# Test_Node.net
KiCad netlist of a schematic drawn in EAGLE
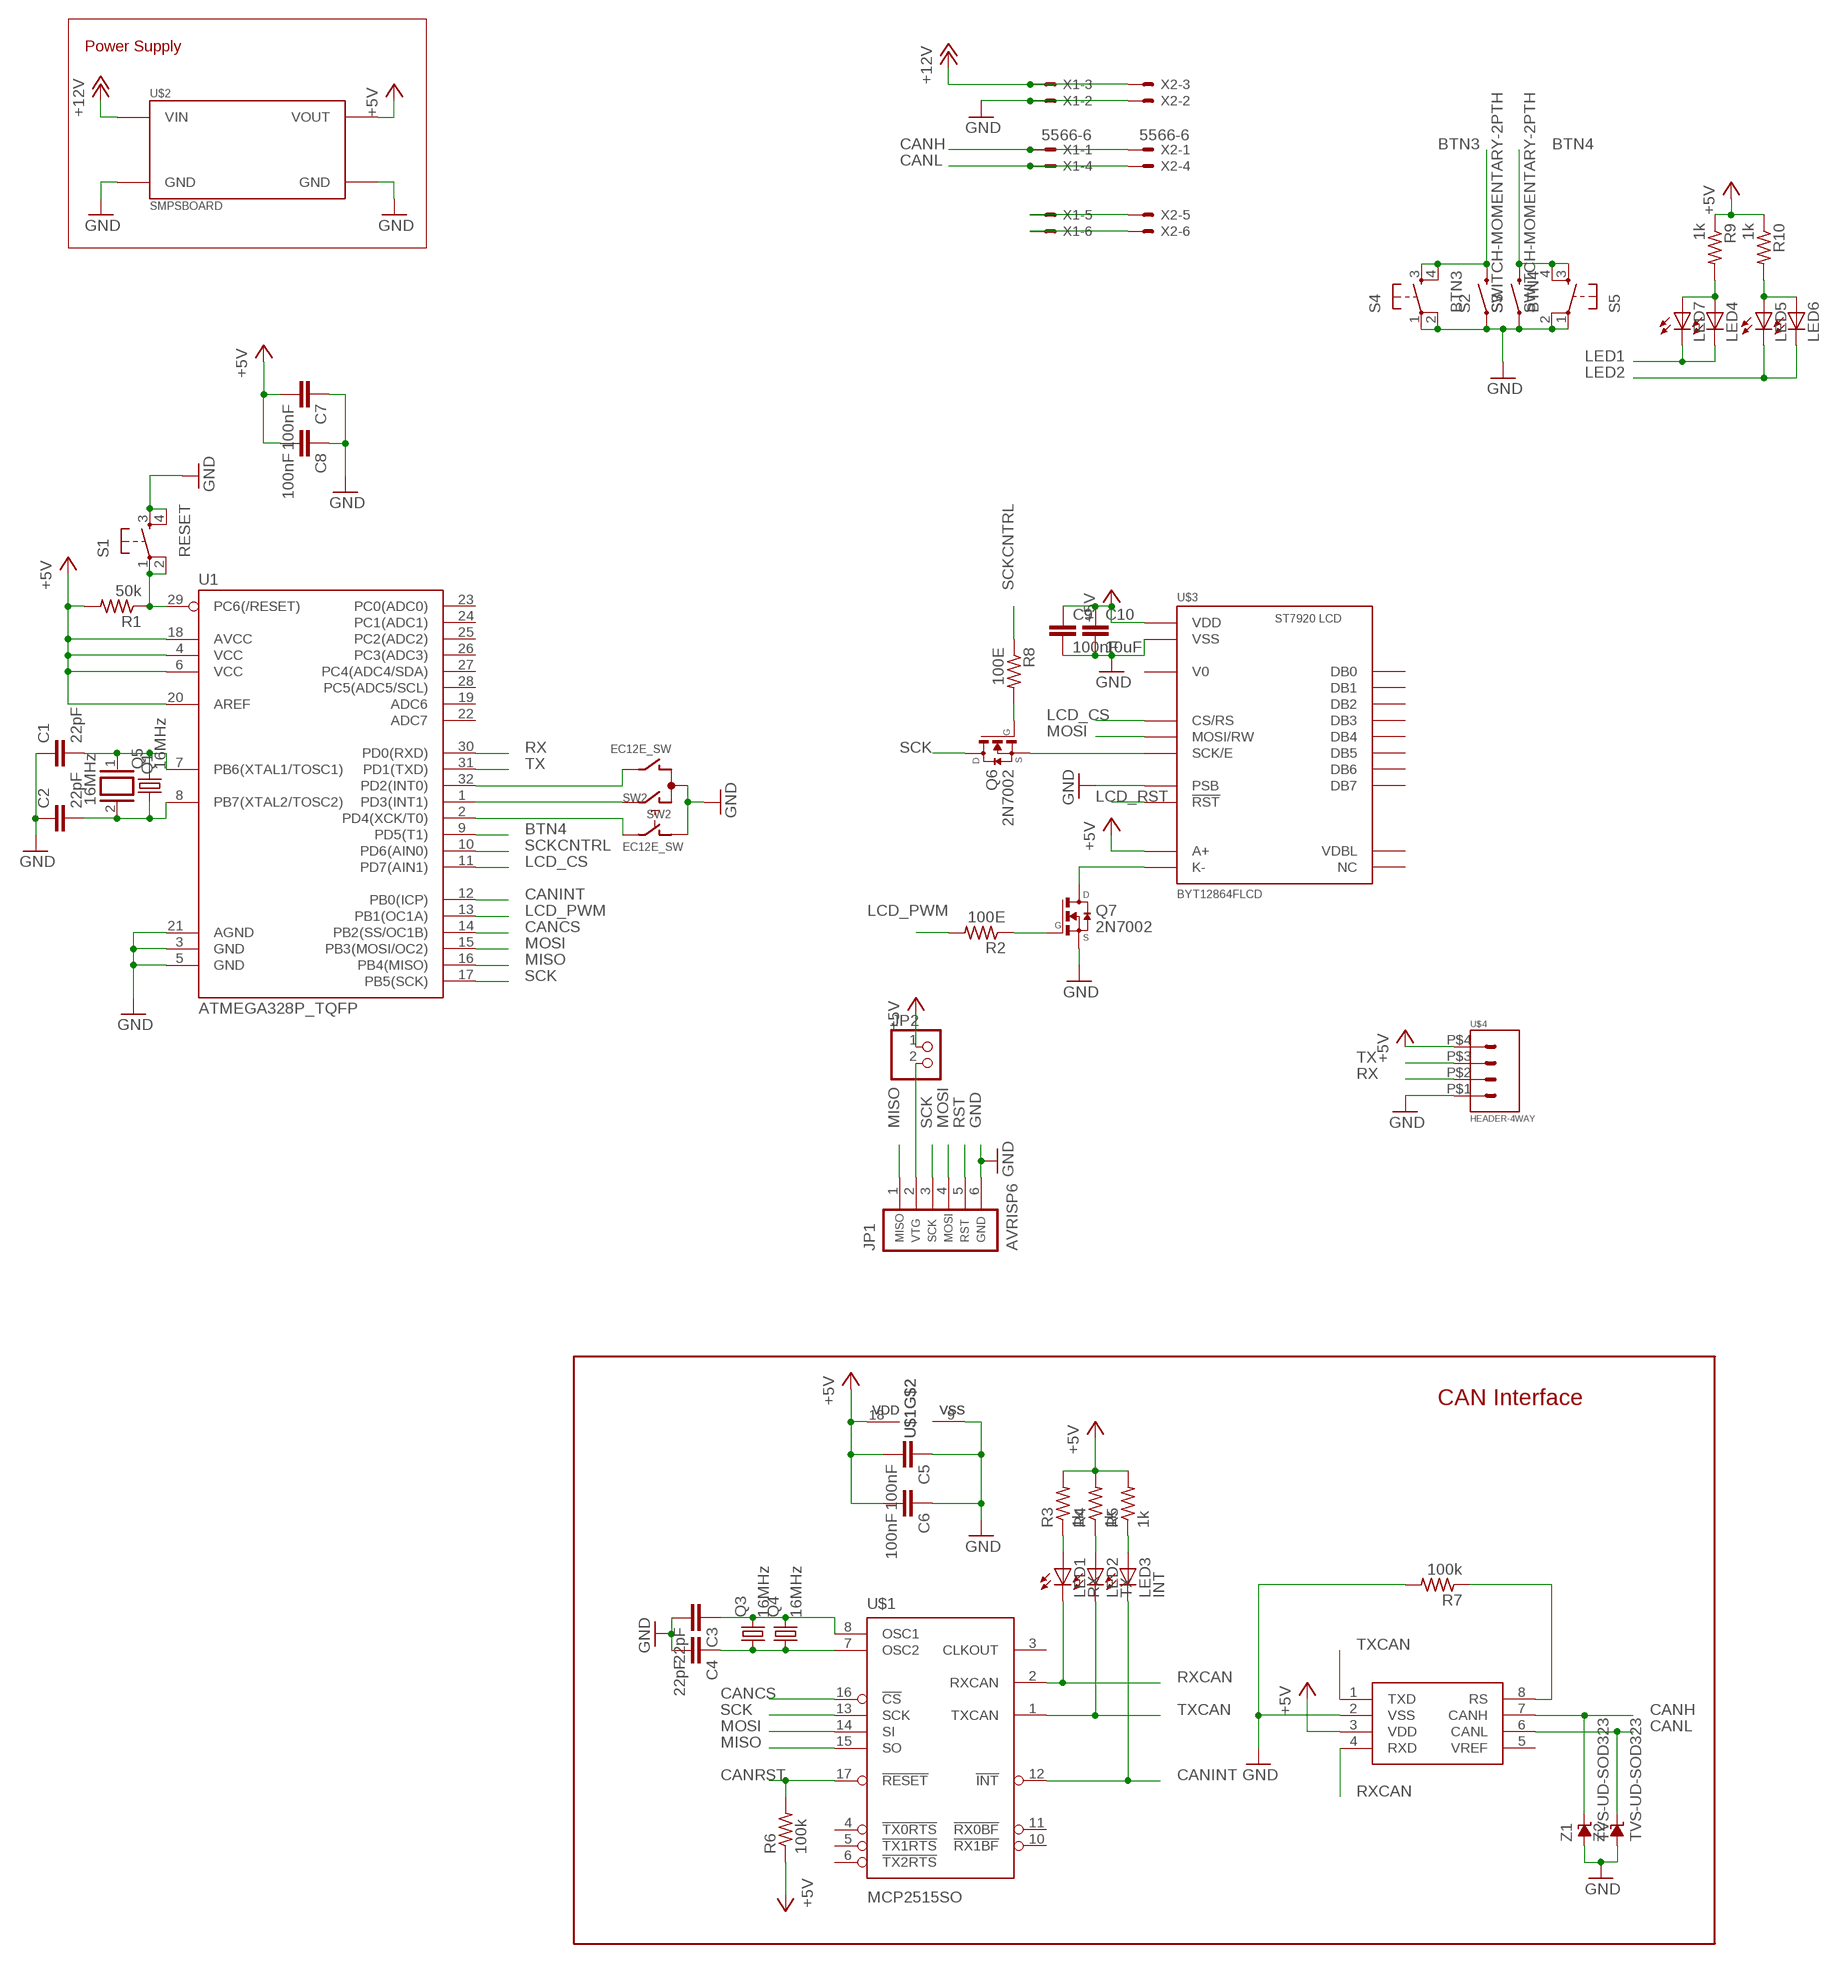
[diagram p0: schematic, sheet 1]

(export (version "E")
  (design (tool "Eeschema 10.0.6"))
  (components
    (comp (ref "C1")
      (value "22pF")
      (footprint "eagle-import:C0805")
      (libsource (lib "eagle-import") (part "C-EUC0805"))
    )
    (comp (ref "C2")
      (value "22pF")
      (footprint "eagle-import:C0805")
      (libsource (lib "eagle-import") (part "C-EUC0805"))
    )
    (comp (ref "C3")
      (value "22pF")
      (footprint "eagle-import:C0805K")
      (libsource (lib "eagle-import") (part "C-EUC0805K"))
    )
    (comp (ref "C4")
      (value "22pF")
      (footprint "eagle-import:C0805K")
      (libsource (lib "eagle-import") (part "C-EUC0805K"))
    )
    (comp (ref "C5")
      (value "100nF")
      (footprint "eagle-import:C0805K")
      (libsource (lib "eagle-import") (part "C-EUC0805K"))
    )
    (comp (ref "C6")
      (value "100nF")
      (footprint "eagle-import:C0805K")
      (libsource (lib "eagle-import") (part "C-EUC0805K"))
    )
    (comp (ref "C7")
      (value "100nF")
      (footprint "eagle-import:C0805")
      (libsource (lib "eagle-import") (part "C-EUC0805"))
    )
    (comp (ref "C8")
      (value "100nF")
      (footprint "eagle-import:C0805")
      (libsource (lib "eagle-import") (part "C-EUC0805"))
    )
    (comp (ref "C9")
      (value "100nF")
      (footprint "eagle-import:C0805")
      (libsource (lib "eagle-import") (part "C-EUC0805"))
    )
    (comp (ref "C10")
      (value "10uF")
      (footprint "eagle-import:C0805")
      (libsource (lib "eagle-import") (part "C-EUC0805"))
    )
    (comp (ref "JP1")
      (value "AVRISP6")
      (footprint "eagle-import:HDR-75869-131")
      (libsource (lib "eagle-import") (part "AVR-ISP6-75869-131"))
    )
    (comp (ref "JP2")
      (value "PINHD-1X2")
      (footprint "eagle-import:1X02")
      (libsource (lib "eagle-import") (part "PINHD-1X2"))
    )
    (comp (ref "LED1")
      (value "RX")
      (footprint "eagle-import:CHIP-LED0805")
      (libsource (lib "eagle-import") (part "LEDCHIP-LED0805"))
    )
    (comp (ref "LED2")
      (value "TX")
      (footprint "eagle-import:CHIP-LED0805")
      (libsource (lib "eagle-import") (part "LEDCHIP-LED0805"))
    )
    (comp (ref "LED3")
      (value "INT")
      (footprint "eagle-import:CHIP-LED0805")
      (libsource (lib "eagle-import") (part "LEDCHIP-LED0805"))
    )
    (comp (ref "LED4")
      (value "LEDCHIP-LED0805")
      (footprint "eagle-import:CHIP-LED0805")
      (libsource (lib "eagle-import") (part "LEDCHIP-LED0805"))
    )
    (comp (ref "LED5")
      (value "LEDCHIP-LED0805")
      (footprint "eagle-import:CHIP-LED0805")
      (libsource (lib "eagle-import") (part "LEDCHIP-LED0805"))
    )
    (comp (ref "LED6")
      (value "LED5MM")
      (footprint "eagle-import:LED5MM")
      (libsource (lib "eagle-import") (part "LED5MM"))
    )
    (comp (ref "LED7")
      (value "LED5MM")
      (footprint "eagle-import:LED5MM")
      (libsource (lib "eagle-import") (part "LED5MM"))
    )
    (comp (ref "Q1")
      (value "16MHz")
      (footprint "eagle-import:QS")
      (libsource (lib "eagle-import") (part "XTAL/S"))
    )
    (comp (ref "Q3")
      (value "16MHz")
      (footprint "eagle-import:HC49_S")
      (libsource (lib "eagle-import") (part "CRYSTALHC49S"))
    )
    (comp (ref "Q4")
      (value "16MHz")
      (footprint "eagle-import:HC49UP")
      (libsource (lib "eagle-import") (part "CRYSTALHC49UP"))
    )
    (comp (ref "Q5")
      (value "16MHz")
      (footprint "eagle-import:HC49UP")
      (libsource (lib "eagle-import") (part "CRYSTALHC49UP"))
    )
    (comp (ref "Q6")
      (value "2N7002")
      (footprint "eagle-import:SOT23")
      (libsource (lib "eagle-import") (part "2N7002"))
    )
    (comp (ref "Q7")
      (value "2N7002")
      (footprint "eagle-import:SOT23")
      (libsource (lib "eagle-import") (part "2N7002"))
    )
    (comp (ref "R1")
      (value "50k")
      (footprint "eagle-import:R0805")
      (libsource (lib "eagle-import") (part "R-US_R0805"))
    )
    (comp (ref "R2")
      (value "100E")
      (footprint "eagle-import:R0805")
      (libsource (lib "eagle-import") (part "R-US_R0805"))
    )
    (comp (ref "R3")
      (value "1k")
      (footprint "eagle-import:R0805")
      (libsource (lib "eagle-import") (part "R-US_R0805"))
    )
    (comp (ref "R4")
      (value "1k")
      (footprint "eagle-import:R0805")
      (libsource (lib "eagle-import") (part "R-US_R0805"))
    )
    (comp (ref "R5")
      (value "1k")
      (footprint "eagle-import:R0805")
      (libsource (lib "eagle-import") (part "R-US_R0805"))
    )
    (comp (ref "R6")
      (value "100k")
      (footprint "eagle-import:R0805")
      (libsource (lib "eagle-import") (part "R-US_R0805"))
    )
    (comp (ref "R7")
      (value "100k")
      (footprint "eagle-import:R0805")
      (libsource (lib "eagle-import") (part "R-US_R0805"))
    )
    (comp (ref "R8")
      (value "100E")
      (footprint "eagle-import:R0805")
      (libsource (lib "eagle-import") (part "R-US_R0805"))
    )
    (comp (ref "R9")
      (value "1k")
      (footprint "eagle-import:R0805")
      (libsource (lib "eagle-import") (part "R-US_R0805"))
    )
    (comp (ref "R10")
      (value "1k")
      (footprint "eagle-import:R0805")
      (libsource (lib "eagle-import") (part "R-US_R0805"))
    )
    (comp (ref "S1")
      (value "RESET")
      (footprint "eagle-import:TACTILE_SWITCH_SMD")
      (libsource (lib "eagle-import") (part "TAC_SWITCHSMD"))
    )
    (comp (ref "S2")
      (value "SWITCH-MOMENTARY-2PTH")
      (footprint "eagle-import:TACTILE-PTH")
      (libsource (lib "eagle-import") (part "SWITCH-MOMENTARY-2PTH"))
    )
    (comp (ref "S3")
      (value "SWITCH-MOMENTARY-2PTH")
      (footprint "eagle-import:TACTILE-PTH")
      (libsource (lib "eagle-import") (part "SWITCH-MOMENTARY-2PTH"))
    )
    (comp (ref "S4")
      (value "BTN3")
      (footprint "eagle-import:TACTILE_SWITCH_SMD")
      (libsource (lib "eagle-import") (part "TAC_SWITCHSMD"))
    )
    (comp (ref "S5")
      (value "BTN4")
      (footprint "eagle-import:TACTILE_SWITCH_SMD")
      (libsource (lib "eagle-import") (part "TAC_SWITCHSMD"))
    )
    (comp (ref "SW2")
      (value "EC12E_SW")
      (footprint "eagle-import:ALPS_EC12E_SW")
      (fields (field (name "MPN") "EC12E2424407"))
      (libsource (lib "eagle-import") (part "EC12E_SW"))
    )
    (comp (ref "U$1")
      (value "MCP2515SO")
      (footprint "eagle-import:SO-18W")
      (libsource (lib "eagle-import") (part "MCP2515SO"))
    )
    (comp (ref "U$2")
      (value "SMPSBOARD")
      (footprint "eagle-import:SMPSBOARD")
      (libsource (lib "eagle-import") (part "SMPSBOARD"))
    )
    (comp (ref "U$3")
      (value "BYT12864FLCD")
      (footprint "eagle-import:BYT12864F")
      (libsource (lib "eagle-import") (part "BYT12864FLCD"))
    )
    (comp (ref "U$4")
      (value "HEADER-4WAY")
      (footprint "eagle-import:1744426-4")
      (libsource (lib "eagle-import") (part "HEADER-4WAY"))
    )
    (comp (ref "U1")
      (value "ATMEGA328P_TQFP")
      (footprint "eagle-import:TQFP32-08")
      (libsource (lib "eagle-import") (part "ATMEGA328P_TQFP"))
    )
    (comp (ref "U2")
      (value "MCP2551")
      (footprint "eagle-import:SO08")
      (libsource (lib "eagle-import") (part "MCP2551"))
    )
    (comp (ref "X1")
      (value "5566-6")
      (footprint "eagle-import:5566-6")
      (fields (field (name "MPN") "95566-61002"))
      (libsource (lib "eagle-import") (part "5566-6"))
    )
    (comp (ref "X2")
      (value "5566-6")
      (footprint "eagle-import:5566-6")
      (fields (field (name "MPN") "95566-61002"))
      (libsource (lib "eagle-import") (part "5566-6"))
    )
    (comp (ref "Z1")
      (value "TVS-UD-SOD323")
      (footprint "eagle-import:SOD323")
      (libsource (lib "eagle-import") (part "TVS-UD-SOD323"))
    )
    (comp (ref "Z2")
      (value "TVS-UD-SOD323")
      (footprint "eagle-import:SOD323")
      (libsource (lib "eagle-import") (part "TVS-UD-SOD323"))
    )
  )
  (nets
    (net (code "1") (name "+5V") (class "Default")
      (node (ref "C10") (pin "1") (pinfunction "1_1") (pintype "passive"))
      (node (ref "C5") (pin "2") (pinfunction "2_2") (pintype "passive"))
      (node (ref "C6") (pin "2") (pinfunction "2_2") (pintype "passive"))
      (node (ref "C7") (pin "2") (pinfunction "2_2") (pintype "passive"))
      (node (ref "C8") (pin "2") (pinfunction "2_2") (pintype "passive"))
      (node (ref "C9") (pin "1") (pinfunction "1_1") (pintype "passive"))
      (node (ref "JP2") (pin "1") (pinfunction "1_1") (pintype "passive"))
      (node (ref "R1") (pin "2") (pinfunction "2_2") (pintype "passive"))
      (node (ref "R10") (pin "1") (pinfunction "1_1") (pintype "passive"))
      (node (ref "R3") (pin "2") (pinfunction "2_2") (pintype "passive"))
      (node (ref "R4") (pin "2") (pinfunction "2_2") (pintype "passive"))
      (node (ref "R5") (pin "2") (pinfunction "2_2") (pintype "passive"))
      (node (ref "R6") (pin "1") (pinfunction "1_1") (pintype "passive"))
      (node (ref "R9") (pin "1") (pinfunction "1_1") (pintype "passive"))
      (node (ref "U$1") (pin "18") (pinfunction "VDD_18") (pintype "power_in"))
      (node (ref "U$2") (pin "VOUT") (pinfunction "VOUT_VOUT") (pintype "bidirectional"))
      (node (ref "U$3") (pin "P$19") (pinfunction "VDD_P$19") (pintype "bidirectional"))
      (node (ref "U$3") (pin "P$2") (pinfunction "A+_P$2") (pintype "bidirectional"))
      (node (ref "U$4") (pin "P$4") (pinfunction "P$4_P$4") (pintype "passive"))
      (node (ref "U1") (pin "18") (pinfunction "AVCC_18") (pintype "bidirectional"))
      (node (ref "U1") (pin "20") (pinfunction "AREF_20") (pintype "bidirectional"))
      (node (ref "U1") (pin "4") (pinfunction "VCC_4") (pintype "bidirectional"))
      (node (ref "U1") (pin "6") (pinfunction "VCC_6") (pintype "bidirectional"))
      (node (ref "U2") (pin "3") (pinfunction "VDD_3") (pintype "bidirectional"))
    )
    (net (code "2") (name "+12V") (class "Default")
      (node (ref "U$2") (pin "VIN") (pinfunction "VIN_VIN") (pintype "bidirectional"))
      (node (ref "X1") (pin "3") (pinfunction "S_3") (pintype "passive"))
      (node (ref "X2") (pin "3") (pinfunction "S_3") (pintype "passive"))
    )
    (net (code "3") (name "/BTN3") (class "Default")
      (node (ref "S2") (pin "3") (pinfunction "2_3") (pintype "passive"))
      (node (ref "S4") (pin "3") (pinfunction "3_3") (pintype "passive"))
      (node (ref "S4") (pin "4") (pinfunction "4_4") (pintype "passive"))
    )
    (net (code "4") (name "/BTN4") (class "Default")
      (node (ref "S3") (pin "3") (pinfunction "2_3") (pintype "passive"))
      (node (ref "S5") (pin "3") (pinfunction "3_3") (pintype "passive"))
      (node (ref "S5") (pin "4") (pinfunction "4_4") (pintype "passive"))
      (node (ref "U1") (pin "9") (pinfunction "PD5(T1)_9") (pintype "bidirectional"))
    )
    (net (code "5") (name "/CANCS") (class "Default")
      (node (ref "U$1") (pin "16") (pinfunction "~{CS}_16") (pintype "input"))
      (node (ref "U1") (pin "14") (pinfunction "PB2(SS/OC1B)_14") (pintype "bidirectional"))
    )
    (net (code "6") (name "/CANH") (class "Default")
      (node (ref "U2") (pin "7") (pinfunction "CANH_7") (pintype "bidirectional"))
      (node (ref "X1") (pin "1") (pinfunction "S_1") (pintype "passive"))
      (node (ref "X2") (pin "1") (pinfunction "S_1") (pintype "passive"))
      (node (ref "Z1") (pin "C") (pinfunction "C_C") (pintype "passive"))
    )
    (net (code "7") (name "/CANINT") (class "Default")
      (node (ref "LED3") (pin "C") (pinfunction "C_C") (pintype "passive"))
      (node (ref "U$1") (pin "12") (pinfunction "~{INT}_12") (pintype "output"))
      (node (ref "U1") (pin "12") (pinfunction "PB0(ICP)_12") (pintype "bidirectional"))
    )
    (net (code "8") (name "/CANL") (class "Default")
      (node (ref "U2") (pin "6") (pinfunction "CANL_6") (pintype "bidirectional"))
      (node (ref "X1") (pin "4") (pinfunction "S_4") (pintype "passive"))
      (node (ref "X2") (pin "4") (pinfunction "S_4") (pintype "passive"))
      (node (ref "Z2") (pin "C") (pinfunction "C_C") (pintype "passive"))
    )
    (net (code "9") (name "/CANRST") (class "Default")
      (node (ref "R6") (pin "2") (pinfunction "2_2") (pintype "passive"))
      (node (ref "U$1") (pin "17") (pinfunction "~{RESET}_17") (pintype "input"))
    )
    (net (code "10") (name "/LCD_CS") (class "Default")
      (node (ref "U$3") (pin "P$17") (pinfunction "CS/RS_P$17") (pintype "bidirectional"))
      (node (ref "U1") (pin "11") (pinfunction "PD7(AIN1)_11") (pintype "bidirectional"))
    )
    (net (code "11") (name "/LCD_PWM") (class "Default")
      (node (ref "R2") (pin "2") (pinfunction "2_2") (pintype "passive"))
      (node (ref "U1") (pin "13") (pinfunction "PB1(OC1A)_13") (pintype "bidirectional"))
    )
    (net (code "12") (name "/LCD_RST") (class "Default")
      (node (ref "U$3") (pin "P$4") (pinfunction "~{RST}_P$4") (pintype "bidirectional"))
    )
    (net (code "13") (name "/LED1") (class "Default")
      (node (ref "LED4") (pin "C") (pinfunction "C_C") (pintype "passive"))
      (node (ref "LED7") (pin "K") (pinfunction "C_K") (pintype "passive"))
    )
    (net (code "14") (name "/LED2") (class "Default")
      (node (ref "LED5") (pin "C") (pinfunction "C_C") (pintype "passive"))
      (node (ref "LED6") (pin "K") (pinfunction "C_K") (pintype "passive"))
    )
    (net (code "15") (name "/MISO") (class "Default")
      (node (ref "JP1") (pin "1") (pinfunction "1_1") (pintype "passive"))
      (node (ref "U$1") (pin "15") (pinfunction "SO_15") (pintype "output"))
      (node (ref "U1") (pin "16") (pinfunction "PB4(MISO)_16") (pintype "bidirectional"))
    )
    (net (code "16") (name "/MOSI") (class "Default")
      (node (ref "JP1") (pin "4") (pinfunction "4_4") (pintype "passive"))
      (node (ref "U$1") (pin "14") (pinfunction "SI_14") (pintype "input"))
      (node (ref "U$3") (pin "P$16") (pinfunction "MOSI/RW_P$16") (pintype "bidirectional"))
      (node (ref "U1") (pin "15") (pinfunction "PB3(MOSI/OC2)_15") (pintype "bidirectional"))
    )
    (net (code "17") (name "/RST") (class "Default")
      (node (ref "JP1") (pin "5") (pinfunction "5_5") (pintype "passive"))
      (node (ref "R1") (pin "1") (pinfunction "1_1") (pintype "passive"))
      (node (ref "S1") (pin "1") (pinfunction "1_1") (pintype "passive"))
      (node (ref "S1") (pin "2") (pinfunction "2_2") (pintype "passive"))
      (node (ref "U1") (pin "29") (pinfunction "PC6(/RESET)_29") (pintype "bidirectional"))
    )
    (net (code "18") (name "/RX") (class "Default")
      (node (ref "U$4") (pin "P$2") (pinfunction "P$2_P$2") (pintype "passive"))
      (node (ref "U1") (pin "30") (pinfunction "PD0(RXD)_30") (pintype "bidirectional"))
    )
    (net (code "19") (name "/RXCAN") (class "Default")
      (node (ref "LED1") (pin "C") (pinfunction "C_C") (pintype "passive"))
      (node (ref "U$1") (pin "2") (pinfunction "RXCAN_2") (pintype "input"))
      (node (ref "U2") (pin "4") (pinfunction "RXD_4") (pintype "bidirectional"))
    )
    (net (code "20") (name "/SCK") (class "Default")
      (node (ref "JP1") (pin "3") (pinfunction "3_3") (pintype "passive"))
      (node (ref "Q6") (pin "3") (pinfunction "D_3") (pintype "passive"))
      (node (ref "U$1") (pin "13") (pinfunction "SCK_13") (pintype "input"))
      (node (ref "U1") (pin "17") (pinfunction "PB5(SCK)_17") (pintype "bidirectional"))
    )
    (net (code "21") (name "/SCKCNTRL") (class "Default")
      (node (ref "R8") (pin "1") (pinfunction "1_1") (pintype "passive"))
      (node (ref "U1") (pin "10") (pinfunction "PD6(AIN0)_10") (pintype "bidirectional"))
    )
    (net (code "22") (name "/TX") (class "Default")
      (node (ref "U$4") (pin "P$3") (pinfunction "P$3_P$3") (pintype "passive"))
      (node (ref "U1") (pin "31") (pinfunction "PD1(TXD)_31") (pintype "bidirectional"))
    )
    (net (code "23") (name "/TXCAN") (class "Default")
      (node (ref "LED2") (pin "C") (pinfunction "C_C") (pintype "passive"))
      (node (ref "U$1") (pin "1") (pinfunction "TXCAN_1") (pintype "output"))
      (node (ref "U2") (pin "1") (pinfunction "TXD_1") (pintype "bidirectional"))
    )
    (net (code "24") (name "GND") (class "Default")
      (node (ref "C1") (pin "1") (pinfunction "1_1") (pintype "passive"))
      (node (ref "C10") (pin "2") (pinfunction "2_2") (pintype "passive"))
      (node (ref "C2") (pin "1") (pinfunction "1_1") (pintype "passive"))
      (node (ref "C3") (pin "2") (pinfunction "2_2") (pintype "passive"))
      (node (ref "C4") (pin "2") (pinfunction "2_2") (pintype "passive"))
      (node (ref "C5") (pin "1") (pinfunction "1_1") (pintype "passive"))
      (node (ref "C6") (pin "1") (pinfunction "1_1") (pintype "passive"))
      (node (ref "C7") (pin "1") (pinfunction "1_1") (pintype "passive"))
      (node (ref "C8") (pin "1") (pinfunction "1_1") (pintype "passive"))
      (node (ref "C9") (pin "2") (pinfunction "2_2") (pintype "passive"))
      (node (ref "JP1") (pin "6") (pinfunction "6_6") (pintype "passive"))
      (node (ref "Q7") (pin "2") (pinfunction "S_2") (pintype "passive"))
      (node (ref "R7") (pin "2") (pinfunction "2_2") (pintype "passive"))
      (node (ref "S1") (pin "3") (pinfunction "3_3") (pintype "passive"))
      (node (ref "S1") (pin "4") (pinfunction "4_4") (pintype "passive"))
      (node (ref "S2") (pin "1") (pinfunction "1_1") (pintype "passive"))
      (node (ref "S3") (pin "1") (pinfunction "1_1") (pintype "passive"))
      (node (ref "S4") (pin "1") (pinfunction "1_1") (pintype "passive"))
      (node (ref "S4") (pin "2") (pinfunction "2_2") (pintype "passive"))
      (node (ref "S5") (pin "1") (pinfunction "1_1") (pintype "passive"))
      (node (ref "S5") (pin "2") (pinfunction "2_2") (pintype "passive"))
      (node (ref "SW2") (pin "C") (pinfunction "C_C") (pintype "passive"))
      (node (ref "SW2") (pin "D") (pinfunction "1_D") (pintype "passive"))
      (node (ref "U$1") (pin "9") (pinfunction "VSS_9") (pintype "power_in"))
      (node (ref "U$2") (pin "GND") (pinfunction "GND_GND") (pintype "bidirectional"))
      (node (ref "U$2") (pin "GND@") (pinfunction "GND_GND@") (pintype "bidirectional"))
      (node (ref "U$3") (pin "P$20") (pinfunction "VSS_P$20") (pintype "bidirectional"))
      (node (ref "U$3") (pin "P$6") (pinfunction "PSB_P$6") (pintype "bidirectional"))
      (node (ref "U$4") (pin "P$1") (pinfunction "P$1_P$1") (pintype "passive"))
      (node (ref "U1") (pin "21") (pinfunction "AGND_21") (pintype "bidirectional"))
      (node (ref "U1") (pin "3") (pinfunction "GND_3") (pintype "bidirectional"))
      (node (ref "U1") (pin "5") (pinfunction "GND_5") (pintype "bidirectional"))
      (node (ref "U2") (pin "2") (pinfunction "VSS_2") (pintype "bidirectional"))
      (node (ref "X1") (pin "2") (pinfunction "S_2") (pintype "passive"))
      (node (ref "X2") (pin "2") (pinfunction "S_2") (pintype "passive"))
      (node (ref "Z1") (pin "A") (pinfunction "A_A") (pintype "passive"))
      (node (ref "Z2") (pin "A") (pinfunction "A_A") (pintype "passive"))
    )
    (net (code "25") (name "Net-(JP1-Pad2)") (class "Default")
      (node (ref "JP1") (pin "2") (pinfunction "2_2") (pintype "passive"))
      (node (ref "JP2") (pin "2") (pinfunction "2_2") (pintype "passive"))
    )
    (net (code "26") (name "Net-(LED1-PadA)") (class "Default")
      (node (ref "LED1") (pin "A") (pinfunction "A_A") (pintype "passive"))
      (node (ref "R3") (pin "1") (pinfunction "1_1") (pintype "passive"))
    )
    (net (code "27") (name "Net-(LED2-PadA)") (class "Default")
      (node (ref "LED2") (pin "A") (pinfunction "A_A") (pintype "passive"))
      (node (ref "R4") (pin "1") (pinfunction "1_1") (pintype "passive"))
    )
    (net (code "28") (name "Net-(LED3-PadA)") (class "Default")
      (node (ref "LED3") (pin "A") (pinfunction "A_A") (pintype "passive"))
      (node (ref "R5") (pin "1") (pinfunction "1_1") (pintype "passive"))
    )
    (net (code "29") (name "Net-(LED4-PadA)") (class "Default")
      (node (ref "LED4") (pin "A") (pinfunction "A_A") (pintype "passive"))
      (node (ref "LED7") (pin "A") (pinfunction "A_A") (pintype "passive"))
      (node (ref "R9") (pin "2") (pinfunction "2_2") (pintype "passive"))
    )
    (net (code "30") (name "Net-(LED5-PadA)") (class "Default")
      (node (ref "LED5") (pin "A") (pinfunction "A_A") (pintype "passive"))
      (node (ref "LED6") (pin "A") (pinfunction "A_A") (pintype "passive"))
      (node (ref "R10") (pin "2") (pinfunction "2_2") (pintype "passive"))
    )
    (net (code "31") (name "Net-(Q6-G)") (class "Default")
      (node (ref "Q6") (pin "1") (pinfunction "G_1") (pintype "passive"))
      (node (ref "R8") (pin "2") (pinfunction "2_2") (pintype "passive"))
    )
    (net (code "32") (name "Net-(Q6-S)") (class "Default")
      (node (ref "Q6") (pin "2") (pinfunction "S_2") (pintype "passive"))
      (node (ref "U$3") (pin "P$15") (pinfunction "SCK/E_P$15") (pintype "bidirectional"))
    )
    (net (code "33") (name "Net-(Q7-D)") (class "Default")
      (node (ref "Q7") (pin "3") (pinfunction "D_3") (pintype "passive"))
      (node (ref "U$3") (pin "P$1") (pinfunction "K-_P$1") (pintype "bidirectional"))
    )
    (net (code "34") (name "Net-(Q7-G)") (class "Default")
      (node (ref "Q7") (pin "1") (pinfunction "G_1") (pintype "passive"))
      (node (ref "R2") (pin "1") (pinfunction "1_1") (pintype "passive"))
    )
    (net (code "35") (name "Net-(SW2B-2)") (class "Default")
      (node (ref "SW2") (pin "E") (pinfunction "2_E") (pintype "passive"))
      (node (ref "U1") (pin "2") (pinfunction "PD4(XCK/T0)_2") (pintype "bidirectional"))
    )
    (net (code "36") (name "Net-(U$1A-OSC1)") (class "Default")
      (node (ref "C3") (pin "1") (pinfunction "1_1") (pintype "passive"))
      (node (ref "Q3") (pin "2") (pinfunction "2_2") (pintype "passive"))
      (node (ref "Q4") (pin "2") (pinfunction "2_2") (pintype "passive"))
      (node (ref "U$1") (pin "8") (pinfunction "OSC1_8") (pintype "input"))
    )
    (net (code "37") (name "Net-(U$1A-OSC2)") (class "Default")
      (node (ref "C4") (pin "1") (pinfunction "1_1") (pintype "passive"))
      (node (ref "Q3") (pin "1") (pinfunction "1_1") (pintype "passive"))
      (node (ref "Q4") (pin "1") (pinfunction "1_1") (pintype "passive"))
      (node (ref "U$1") (pin "7") (pinfunction "OSC2_7") (pintype "output"))
    )
    (net (code "38") (name "Net-(U1-PB6(XTAL1{slash}TOSC1))") (class "Default")
      (node (ref "C1") (pin "2") (pinfunction "2_2") (pintype "passive"))
      (node (ref "Q1") (pin "1") (pinfunction "1_1") (pintype "passive"))
      (node (ref "Q5") (pin "2") (pinfunction "2_2") (pintype "passive"))
      (node (ref "U1") (pin "7") (pinfunction "PB6(XTAL1/TOSC1)_7") (pintype "bidirectional"))
    )
    (net (code "39") (name "Net-(U1-PB7(XTAL2{slash}TOSC2))") (class "Default")
      (node (ref "C2") (pin "2") (pinfunction "2_2") (pintype "passive"))
      (node (ref "Q1") (pin "2") (pinfunction "2_2") (pintype "passive"))
      (node (ref "Q5") (pin "1") (pinfunction "1_1") (pintype "passive"))
      (node (ref "U1") (pin "8") (pinfunction "PB7(XTAL2/TOSC2)_8") (pintype "bidirectional"))
    )
    (net (code "40") (name "Net-(U1-PD2(INT0))") (class "Default")
      (node (ref "SW2") (pin "B") (pinfunction "B_B") (pintype "passive"))
      (node (ref "U1") (pin "32") (pinfunction "PD2(INT0)_32") (pintype "bidirectional"))
    )
    (net (code "41") (name "Net-(U1-PD3(INT1))") (class "Default")
      (node (ref "SW2") (pin "A") (pinfunction "A_A") (pintype "passive"))
      (node (ref "U1") (pin "1") (pinfunction "PD3(INT1)_1") (pintype "bidirectional"))
    )
    (net (code "42") (name "Net-(U2-RS)") (class "Default")
      (node (ref "R7") (pin "1") (pinfunction "1_1") (pintype "passive"))
      (node (ref "U2") (pin "8") (pinfunction "RS_8") (pintype "bidirectional"))
    )
    (net (code "43") (name "Net-(X1E-S)") (class "Default")
      (node (ref "X1") (pin "5") (pinfunction "S_5") (pintype "passive"))
      (node (ref "X2") (pin "5") (pinfunction "S_5") (pintype "passive"))
    )
    (net (code "44") (name "Net-(X1F-S)") (class "Default")
      (node (ref "X1") (pin "6") (pinfunction "S_6") (pintype "passive"))
      (node (ref "X2") (pin "6") (pinfunction "S_6") (pintype "passive"))
    )
    (net (code "45") (name "unconnected-(U$1A-CLKOUT-Pad3)") (class "Default")
      (node (ref "U$1") (pin "3") (pinfunction "CLKOUT_3") (pintype "output"))
    )
    (net (code "46") (name "unconnected-(U$1A-~{RX0BF}-Pad11)") (class "Default")
      (node (ref "U$1") (pin "11") (pinfunction "~{RX0BF}_11") (pintype "output"))
    )
    (net (code "47") (name "unconnected-(U$1A-~{RX1BF}-Pad10)") (class "Default")
      (node (ref "U$1") (pin "10") (pinfunction "~{RX1BF}_10") (pintype "output"))
    )
    (net (code "48") (name "unconnected-(U$1A-~{TX0RTS}-Pad4)") (class "Default")
      (node (ref "U$1") (pin "4") (pinfunction "~{TX0RTS}_4") (pintype "input"))
    )
    (net (code "49") (name "unconnected-(U$1A-~{TX1RTS}-Pad5)") (class "Default")
      (node (ref "U$1") (pin "5") (pinfunction "~{TX1RTS}_5") (pintype "input"))
    )
    (net (code "50") (name "unconnected-(U$1A-~{TX2RTS}-Pad6)") (class "Default")
      (node (ref "U$1") (pin "6") (pinfunction "~{TX2RTS}_6") (pintype "input"))
    )
    (net (code "51") (name "unconnected-(U$3-DB0-PadP$14)") (class "Default")
      (node (ref "U$3") (pin "P$14") (pinfunction "DB0_P$14") (pintype "bidirectional"))
    )
    (net (code "52") (name "unconnected-(U$3-DB1-PadP$13)") (class "Default")
      (node (ref "U$3") (pin "P$13") (pinfunction "DB1_P$13") (pintype "bidirectional"))
    )
    (net (code "53") (name "unconnected-(U$3-DB2-PadP$12)") (class "Default")
      (node (ref "U$3") (pin "P$12") (pinfunction "DB2_P$12") (pintype "bidirectional"))
    )
    (net (code "54") (name "unconnected-(U$3-DB3-PadP$11)") (class "Default")
      (node (ref "U$3") (pin "P$11") (pinfunction "DB3_P$11") (pintype "bidirectional"))
    )
    (net (code "55") (name "unconnected-(U$3-DB4-PadP$10)") (class "Default")
      (node (ref "U$3") (pin "P$10") (pinfunction "DB4_P$10") (pintype "bidirectional"))
    )
    (net (code "56") (name "unconnected-(U$3-DB5-PadP$9)") (class "Default")
      (node (ref "U$3") (pin "P$9") (pinfunction "DB5_P$9") (pintype "bidirectional"))
    )
    (net (code "57") (name "unconnected-(U$3-DB6-PadP$8)") (class "Default")
      (node (ref "U$3") (pin "P$8") (pinfunction "DB6_P$8") (pintype "bidirectional"))
    )
    (net (code "58") (name "unconnected-(U$3-DB7-PadP$7)") (class "Default")
      (node (ref "U$3") (pin "P$7") (pinfunction "DB7_P$7") (pintype "bidirectional"))
    )
    (net (code "59") (name "unconnected-(U$3-NC-PadP$5)") (class "Default")
      (node (ref "U$3") (pin "P$5") (pinfunction "NC_P$5") (pintype "bidirectional"))
    )
    (net (code "60") (name "unconnected-(U$3-V0-PadP$18)") (class "Default")
      (node (ref "U$3") (pin "P$18") (pinfunction "V0_P$18") (pintype "bidirectional"))
    )
    (net (code "61") (name "unconnected-(U$3-VDBL-PadP$3)") (class "Default")
      (node (ref "U$3") (pin "P$3") (pinfunction "VDBL_P$3") (pintype "bidirectional"))
    )
    (net (code "62") (name "unconnected-(U1-ADC6-Pad19)") (class "Default")
      (node (ref "U1") (pin "19") (pinfunction "ADC6_19") (pintype "bidirectional"))
    )
    (net (code "63") (name "unconnected-(U1-ADC7-Pad22)") (class "Default")
      (node (ref "U1") (pin "22") (pinfunction "ADC7_22") (pintype "bidirectional"))
    )
    (net (code "64") (name "unconnected-(U1-PC0(ADC0)-Pad23)") (class "Default")
      (node (ref "U1") (pin "23") (pinfunction "PC0(ADC0)_23") (pintype "bidirectional"))
    )
    (net (code "65") (name "unconnected-(U1-PC1(ADC1)-Pad24)") (class "Default")
      (node (ref "U1") (pin "24") (pinfunction "PC1(ADC1)_24") (pintype "bidirectional"))
    )
    (net (code "66") (name "unconnected-(U1-PC2(ADC2)-Pad25)") (class "Default")
      (node (ref "U1") (pin "25") (pinfunction "PC2(ADC2)_25") (pintype "bidirectional"))
    )
    (net (code "67") (name "unconnected-(U1-PC3(ADC3)-Pad26)") (class "Default")
      (node (ref "U1") (pin "26") (pinfunction "PC3(ADC3)_26") (pintype "bidirectional"))
    )
    (net (code "68") (name "unconnected-(U1-PC4(ADC4{slash}SDA)-Pad27)") (class "Default")
      (node (ref "U1") (pin "27") (pinfunction "PC4(ADC4/SDA)_27") (pintype "bidirectional"))
    )
    (net (code "69") (name "unconnected-(U1-PC5(ADC5{slash}SCL)-Pad28)") (class "Default")
      (node (ref "U1") (pin "28") (pinfunction "PC5(ADC5/SCL)_28") (pintype "bidirectional"))
    )
    (net (code "70") (name "unconnected-(U2-VREF-Pad5)") (class "Default")
      (node (ref "U2") (pin "5") (pinfunction "VREF_5") (pintype "bidirectional"))
    )
  )
)
